# STSPIN.net
KiCad netlist of a schematic drawn in Altium Designer
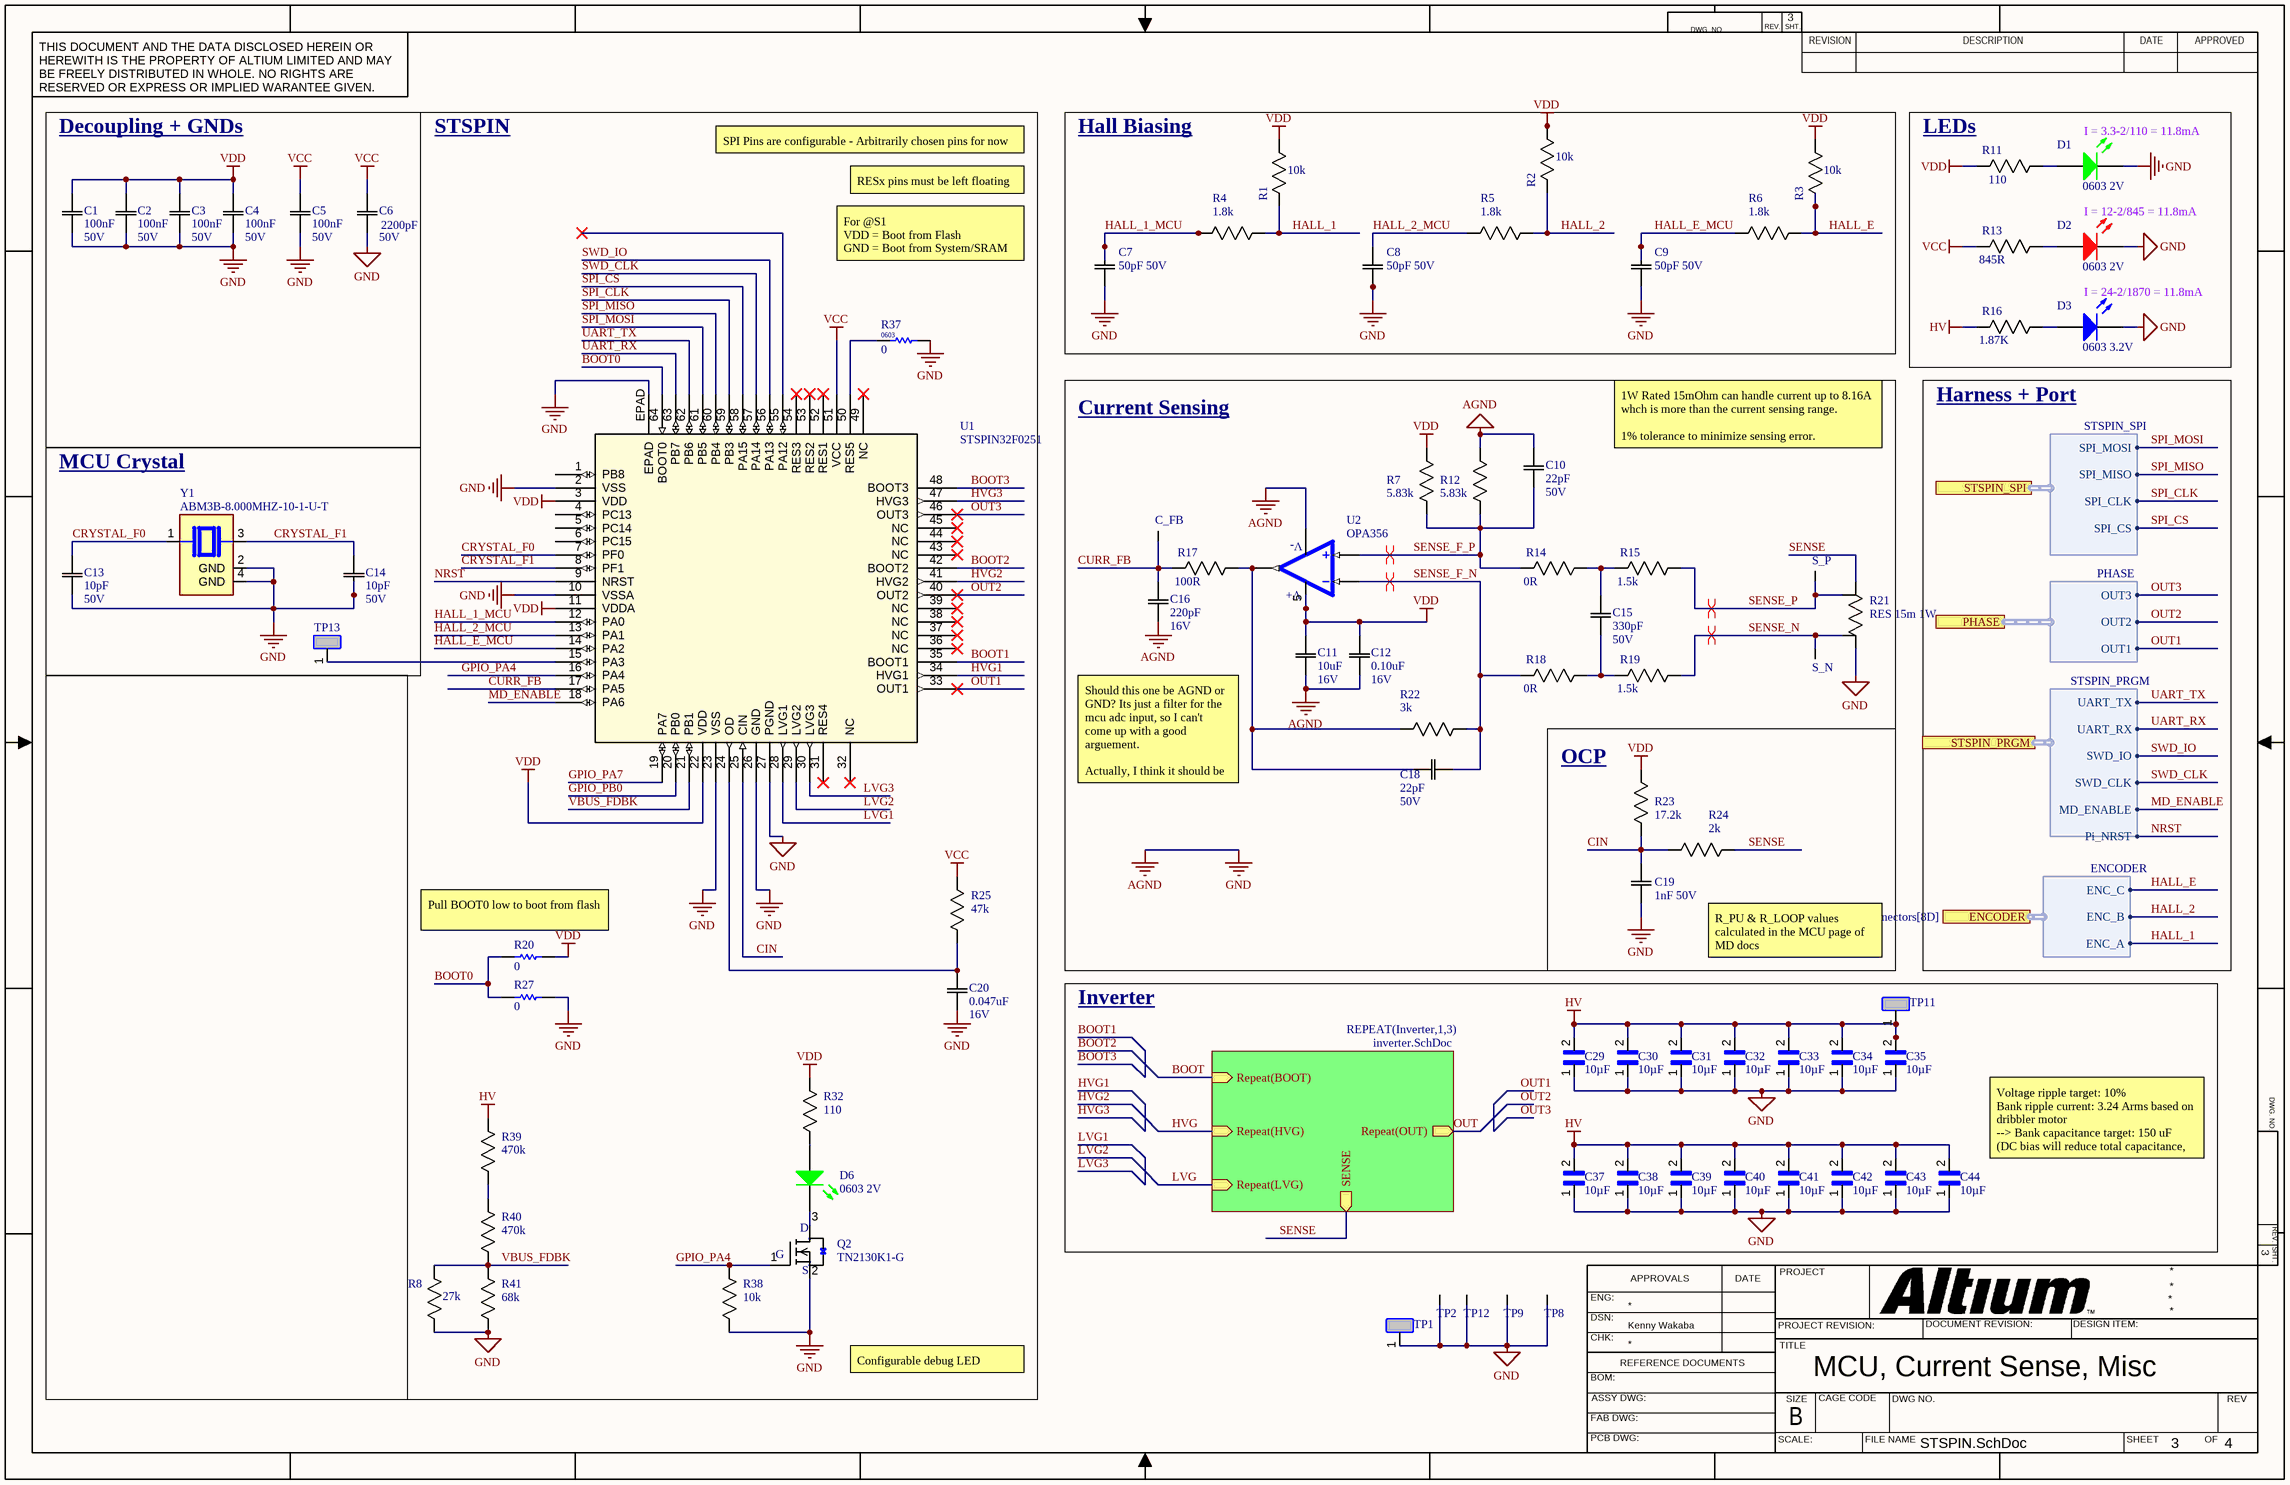
[diagram p0: STSPIN.SchDoc]

(export (version "E")
  (design (tool "Eeschema 10.0.6"))
  (components
    (comp (ref "C1")
      (value "100nF")
      (footprint "0603")
      (description "Default Symbol for Capacitors")
      (fields
        (field (name "RATING") "50V")
        (field (name "PART NUMBER") "CAP 100nF 50V")
        (field (name "TOLERANCE") "10%")
      )
      (libsource (lib "capacitor_library") (part "CAP_Default"))
    )
    (comp (ref "C2")
      (value "100nF")
      (footprint "0603")
      (description "Default Symbol for Capacitors")
      (fields
        (field (name "RATING") "50V")
        (field (name "PART NUMBER") "CAP 100nF 50V")
        (field (name "TOLERANCE") "10%")
      )
      (libsource (lib "capacitor_library") (part "CAP_Default"))
    )
    (comp (ref "C3")
      (value "100nF")
      (footprint "0603")
      (description "Default Symbol for Capacitors")
      (fields
        (field (name "RATING") "50V")
        (field (name "PART NUMBER") "CAP 100nF 50V")
        (field (name "TOLERANCE") "10%")
      )
      (libsource (lib "capacitor_library") (part "CAP_Default"))
    )
    (comp (ref "C4")
      (value "100nF")
      (footprint "0603")
      (description "Default Symbol for Capacitors")
      (fields
        (field (name "RATING") "50V")
        (field (name "PART NUMBER") "CAP 100nF 50V")
        (field (name "TOLERANCE") "10%")
      )
      (libsource (lib "capacitor_library") (part "CAP_Default"))
    )
    (comp (ref "C5")
      (value "100nF")
      (footprint "0603")
      (description "Default Symbol for Capacitors")
      (fields
        (field (name "RATING") "50V")
        (field (name "PART NUMBER") "CAP 100nF 50V")
        (field (name "TOLERANCE") "10%")
      )
      (libsource (lib "capacitor_library") (part "CAP_Default"))
    )
    (comp (ref "C6")
      (value "2200pF")
      (footprint "0603")
      (description "Default Symbol for Capacitors")
      (fields
        (field (name "RATING") "50V")
        (field (name "PART NUMBER") "CAP 2200pF 50V")
        (field (name "TOLERANCE") "10%")
      )
      (libsource (lib "capacitor_library") (part "CAP_Default"))
    )
    (comp (ref "C7")
      (value "50pF 50V")
      (footprint "0603")
      (description "50 pF ±5% 50V Ceramic Capacitor C0G, NP0 0603 (1608 Metric)")
      (fields (field (name "TOLERANCE") "10%"))
      (libsource (lib "MDV6-TEMP") (part "CAP 50pF 50V"))
    )
    (comp (ref "C8")
      (value "50pF 50V")
      (footprint "0603")
      (description "50 pF ±5% 50V Ceramic Capacitor C0G, NP0 0603 (1608 Metric)")
      (fields (field (name "TOLERANCE") "10%"))
      (libsource (lib "MDV6-TEMP") (part "CAP 50pF 50V"))
    )
    (comp (ref "C9")
      (value "50pF 50V")
      (footprint "0603")
      (description "50 pF ±5% 50V Ceramic Capacitor C0G, NP0 0603 (1608 Metric)")
      (fields (field (name "TOLERANCE") "10%"))
      (libsource (lib "MDV6-TEMP") (part "CAP 50pF 50V"))
    )
    (comp (ref "C10")
      (value "22pF")
      (footprint "0603")
      (description "Default Symbol for Capacitors")
      (fields
        (field (name "RATING") "50V")
        (field (name "PART NUMBER") "CAP 22pF 50V")
        (field (name "TOLERANCE") "10%")
      )
      (libsource (lib "capacitor_library") (part "CAP_Default"))
    )
    (comp (ref "C11")
      (value "10uF")
      (footprint "0603")
      (description "CAP CER 10UF 16V X5R 0603/0805")
      (fields
        (field (name "TOLERANCE") "10%")
        (field (name "RATING") "16V")
        (field (name "PART NUMBER") "CAP 10uF 16V")
      )
      (libsource (lib "capacitor_library") (part "CAP 10uF 16V"))
    )
    (comp (ref "C12")
      (value "0.10uF")
      (footprint "0603")
      (description "CAP CER 0.10UF 16V X5R 0603")
      (fields
        (field (name "TOLERANCE") "10%")
        (field (name "RATING") "16V")
        (field (name "PART NUMBER") "CAP 0.10uF 16V")
      )
      (libsource (lib "capacitor_library") (part "CAP 0.10uF 16V"))
    )
    (comp (ref "C13")
      (value "10pF")
      (footprint "0603")
      (description "Default Symbol for Capacitors")
      (fields
        (field (name "RATING") "50V")
        (field (name "PART NUMBER") "CAP 10pF 50V")
        (field (name "TOLERANCE") "10%")
      )
      (libsource (lib "capacitor_library") (part "CAP_Default"))
    )
    (comp (ref "C14")
      (value "10pF")
      (footprint "0603")
      (description "Default Symbol for Capacitors")
      (fields
        (field (name "RATING") "50V")
        (field (name "PART NUMBER") "CAP 10pF 50V")
        (field (name "TOLERANCE") "10%")
      )
      (libsource (lib "capacitor_library") (part "CAP_Default"))
    )
    (comp (ref "C15")
      (value "330pF")
      (footprint "0603")
      (description "Default Symbol for Capacitors")
      (fields
        (field (name "RATING") "50V")
        (field (name "PART NUMBER") "CAP 330pF 50V")
        (field (name "TOLERANCE") "10%")
      )
      (libsource (lib "capacitor_library") (part "CAP_Default"))
    )
    (comp (ref "C16")
      (value "220pF")
      (footprint "0603")
      (description "Default Symbol for Capacitors")
      (fields
        (field (name "RATING") "16V")
        (field (name "PART NUMBER") "CAP 220pF 16V")
        (field (name "TOLERANCE") "10%")
      )
      (libsource (lib "capacitor_library") (part "CAP_Default"))
    )
    (comp (ref "C18")
      (value "22pF")
      (footprint "0603")
      (description "Default Symbol for Capacitors")
      (fields
        (field (name "RATING") "50V")
        (field (name "PART NUMBER") "CAP 22pF 50V")
        (field (name "TOLERANCE") "10%")
      )
      (libsource (lib "capacitor_library") (part "CAP_Default"))
    )
    (comp (ref "C19")
      (value "1nF 50V")
      (footprint "0603")
      (description "CAP CER 0603 1NF 50V X7R 10%")
      (fields (field (name "TOLERANCE") "10%"))
      (libsource (lib "MDV6-TEMP") (part "CAP 1nF 50V"))
    )
    (comp (ref "C20")
      (value "0.047uF")
      (footprint "0603")
      (description "Default Symbol for Capacitors")
      (fields
        (field (name "RATING") "16V")
        (field (name "PART NUMBER") "CAP 0.047uF 16V")
        (field (name "TOLERANCE") "10%")
      )
      (libsource (lib "capacitor_library") (part "CAP_Default"))
    )
    (comp (ref "C29")
      (value "10µF")
      (footprint "CAPC2012X145N")
      (description "SMD capacitor X5R(EIA) with capacitance 10uF Tol.10%. Rated voltage 50Vdc 85C")
      (fields (field (name "MP") "GRM21BR61H106KE43K") (field (name "MF") "Murata"))
      (libsource (lib "UBC Thunderbots") (part "GRM21BR61H106KE43K"))
    )
    (comp (ref "C30")
      (value "10µF")
      (footprint "CAPC2012X145N")
      (description "SMD capacitor X5R(EIA) with capacitance 10uF Tol.10%. Rated voltage 50Vdc 85C")
      (fields (field (name "MP") "GRM21BR61H106KE43K") (field (name "MF") "Murata"))
      (libsource (lib "UBC Thunderbots") (part "GRM21BR61H106KE43K"))
    )
    (comp (ref "C31")
      (value "10µF")
      (footprint "CAPC2012X145N")
      (description "SMD capacitor X5R(EIA) with capacitance 10uF Tol.10%. Rated voltage 50Vdc 85C")
      (fields (field (name "MP") "GRM21BR61H106KE43K") (field (name "MF") "Murata"))
      (libsource (lib "UBC Thunderbots") (part "GRM21BR61H106KE43K"))
    )
    (comp (ref "C32")
      (value "10µF")
      (footprint "CAPC2012X145N")
      (description "SMD capacitor X5R(EIA) with capacitance 10uF Tol.10%. Rated voltage 50Vdc 85C")
      (fields (field (name "MP") "GRM21BR61H106KE43K") (field (name "MF") "Murata"))
      (libsource (lib "UBC Thunderbots") (part "GRM21BR61H106KE43K"))
    )
    (comp (ref "C33")
      (value "10µF")
      (footprint "CAPC2012X145N")
      (description "SMD capacitor X5R(EIA) with capacitance 10uF Tol.10%. Rated voltage 50Vdc 85C")
      (fields (field (name "MP") "GRM21BR61H106KE43K") (field (name "MF") "Murata"))
      (libsource (lib "UBC Thunderbots") (part "GRM21BR61H106KE43K"))
    )
    (comp (ref "C34")
      (value "10µF")
      (footprint "CAPC2012X145N")
      (description "SMD capacitor X5R(EIA) with capacitance 10uF Tol.10%. Rated voltage 50Vdc 85C")
      (fields (field (name "MP") "GRM21BR61H106KE43K") (field (name "MF") "Murata"))
      (libsource (lib "UBC Thunderbots") (part "GRM21BR61H106KE43K"))
    )
    (comp (ref "C35")
      (value "10µF")
      (footprint "CAPC2012X145N")
      (description "SMD capacitor X5R(EIA) with capacitance 10uF Tol.10%. Rated voltage 50Vdc 85C")
      (fields (field (name "MP") "GRM21BR61H106KE43K") (field (name "MF") "Murata"))
      (libsource (lib "UBC Thunderbots") (part "GRM21BR61H106KE43K"))
    )
    (comp (ref "C37")
      (value "10µF")
      (footprint "CAPC2012X145N")
      (description "SMD capacitor X5R(EIA) with capacitance 10uF Tol.10%. Rated voltage 50Vdc 85C")
      (fields (field (name "MP") "GRM21BR61H106KE43K") (field (name "MF") "Murata"))
      (libsource (lib "UBC Thunderbots") (part "GRM21BR61H106KE43K"))
    )
    (comp (ref "C38")
      (value "10µF")
      (footprint "CAPC2012X145N")
      (description "SMD capacitor X5R(EIA) with capacitance 10uF Tol.10%. Rated voltage 50Vdc 85C")
      (fields (field (name "MP") "GRM21BR61H106KE43K") (field (name "MF") "Murata"))
      (libsource (lib "UBC Thunderbots") (part "GRM21BR61H106KE43K"))
    )
    (comp (ref "C39")
      (value "10µF")
      (footprint "CAPC2012X145N")
      (description "SMD capacitor X5R(EIA) with capacitance 10uF Tol.10%. Rated voltage 50Vdc 85C")
      (fields (field (name "MP") "GRM21BR61H106KE43K") (field (name "MF") "Murata"))
      (libsource (lib "UBC Thunderbots") (part "GRM21BR61H106KE43K"))
    )
    (comp (ref "C40")
      (value "10µF")
      (footprint "CAPC2012X145N")
      (description "SMD capacitor X5R(EIA) with capacitance 10uF Tol.10%. Rated voltage 50Vdc 85C")
      (fields (field (name "MP") "GRM21BR61H106KE43K") (field (name "MF") "Murata"))
      (libsource (lib "UBC Thunderbots") (part "GRM21BR61H106KE43K"))
    )
    (comp (ref "C41")
      (value "10µF")
      (footprint "CAPC2012X145N")
      (description "SMD capacitor X5R(EIA) with capacitance 10uF Tol.10%. Rated voltage 50Vdc 85C")
      (fields (field (name "MP") "GRM21BR61H106KE43K") (field (name "MF") "Murata"))
      (libsource (lib "UBC Thunderbots") (part "GRM21BR61H106KE43K"))
    )
    (comp (ref "C42")
      (value "10µF")
      (footprint "CAPC2012X145N")
      (description "SMD capacitor X5R(EIA) with capacitance 10uF Tol.10%. Rated voltage 50Vdc 85C")
      (fields (field (name "MP") "GRM21BR61H106KE43K") (field (name "MF") "Murata"))
      (libsource (lib "UBC Thunderbots") (part "GRM21BR61H106KE43K"))
    )
    (comp (ref "C43")
      (value "10µF")
      (footprint "CAPC2012X145N")
      (description "SMD capacitor X5R(EIA) with capacitance 10uF Tol.10%. Rated voltage 50Vdc 85C")
      (fields (field (name "MP") "GRM21BR61H106KE43K") (field (name "MF") "Murata"))
      (libsource (lib "UBC Thunderbots") (part "GRM21BR61H106KE43K"))
    )
    (comp (ref "C44")
      (value "10µF")
      (footprint "CAPC2012X145N")
      (description "SMD capacitor X5R(EIA) with capacitance 10uF Tol.10%. Rated voltage 50Vdc 85C")
      (fields (field (name "MP") "GRM21BR61H106KE43K") (field (name "MF") "Murata"))
      (libsource (lib "UBC Thunderbots") (part "GRM21BR61H106KE43K"))
    )
    (comp (ref "C_FB")
      (value "Test Point (Via)")
      (footprint "TP")
      (libsource (lib "UBC Thunderbots") (part "Test Point (Via)"))
    )
    (comp (ref "D1")
      (value "0603 2V")
      (footprint "0603 - LED")
      (description "Green 570nm LED Indication - Discrete 2V 0603 (1608 Metric)")
      (libsource (lib "MDV6-TEMP") (part "LED GREEN SMD 0603"))
    )
    (comp (ref "D2")
      (value "0603 2V")
      (footprint "0603 - LED")
      (description "Red 625nm LED Indication - Discrete 2V 0603 (1608 Metric)")
      (libsource (lib "MDV6-TEMP") (part "LED RED SMD 0603"))
    )
    (comp (ref "D3")
      (value "0603 3.2V")
      (footprint "0603 - LED")
      (description "Blue 470nm LED Indication - Discrete 3.2V 0603 (1608 Metric)")
      (libsource (lib "MDV6-TEMP") (part "LED BLUE SMD 0603"))
    )
    (comp (ref "D6")
      (value "0603 2V")
      (footprint "0603 - LED")
      (description "Green 570nm LED Indication - Discrete 2V 0603 (1608 Metric)")
      (libsource (lib "MDV6-TEMP") (part "LED GREEN SMD 0603"))
    )
    (comp (ref "Q2")
      (value "TN2130K1-G")
      (footprint "SOT95P237X112-3N")
      (description "N-Channel 300 V 85mA (Tj) 360mW (Tc) Surface Mount TO-236AB (SOT23)")
      (fields
        (field (name "PART NUMBER") "MOSFET N-CH TN2130K1-G")
        (field (name "COPYRIGHT") "Copyright (C) 2021 Ultra Librarian. All rights reserved.")
      )
      (libsource (lib "Transistor_Library") (part "MOSFET N-CH TN2130K1-G"))
    )
    (comp (ref "R1")
      (value "10k")
      (footprint "0603")
      (description "RES 10k 1/8W - 1%")
      (fields (field (name "TOLERANCE") "5%"))
      (libsource (lib "UBC Thunderbots") (part "RES_DEFAULT"))
    )
    (comp (ref "R2")
      (value "10k")
      (footprint "0603")
      (description "RES 10k 1/8W - 1%")
      (fields (field (name "TOLERANCE") "5%"))
      (libsource (lib "UBC Thunderbots") (part "RES_DEFAULT"))
    )
    (comp (ref "R3")
      (value "10k")
      (footprint "0603")
      (description "RES 10k 1/8W - 1%")
      (fields (field (name "TOLERANCE") "5%"))
      (libsource (lib "UBC Thunderbots") (part "RES_DEFAULT"))
    )
    (comp (ref "R4")
      (value "1.8k")
      (footprint "0603")
      (description "Default Resistor Symbol")
      (fields (field (name "TOLERANCE") "5%") (field (name "PART NUMBER") "RES 1.8k 1/8W"))
      (libsource (lib "") (part "RES_DEFAULT_1"))
    )
    (comp (ref "R5")
      (value "1.8k")
      (footprint "0603")
      (description "Default Resistor Symbol")
      (fields (field (name "TOLERANCE") "5%") (field (name "PART NUMBER") "RES 1.8k 1/8W"))
      (libsource (lib "") (part "RES_DEFAULT_1"))
    )
    (comp (ref "R6")
      (value "1.8k")
      (footprint "0603")
      (description "Default Resistor Symbol")
      (fields (field (name "TOLERANCE") "5%") (field (name "PART NUMBER") "RES 1.8k 1/8W"))
      (libsource (lib "") (part "RES_DEFAULT_1"))
    )
    (comp (ref "R7")
      (value "5.83k")
      (footprint "0603")
      (description "RES 5.83K OHM 0.1% 1/10W 0603")
      (fields (field (name "TOLERANCE") "1%"))
      (libsource (lib "MDV6-TEMP") (part "RES 5.83k 1/10W 0.1%"))
    )
    (comp (ref "R8")
      (value "27k")
      (footprint "0603")
      (description "RES 27k 1/8W")
      (libsource (lib "UBC Thunderbots") (part "RES_DEFAULT"))
    )
    (comp (ref "R11")
      (value "110")
      (footprint "0603")
      (description "Default Resistor Symbol")
      (fields (field (name "TOLERANCE") "1%") (field (name "PART NUMBER") "RES 110.0 1/8W - 1%"))
      (libsource (lib "Resistor_Library") (part "RES_DEFAULT"))
    )
    (comp (ref "R12")
      (value "5.83k")
      (footprint "0603")
      (description "RES 5.83K OHM 0.1% 1/10W 0603")
      (fields (field (name "TOLERANCE") "1%"))
      (libsource (lib "MDV6-TEMP") (part "RES 5.83k 1/10W 0.1%"))
    )
    (comp (ref "R13")
      (value "845R")
      (footprint "0603")
      (description "RES 845 OHM 1% 1/10W 0603")
      (fields (field (name "TOLERANCE") "1%"))
      (libsource (lib "MDV6-TEMP") (part "RES 845 1/10W 1%"))
    )
    (comp (ref "R14")
      (value "0R")
      (footprint "0603")
      (description "0 OHM 1/10W 0603")
      (fields (field (name "TOLERANCE") "1%"))
      (libsource (lib "") (part "RES 100R 1/10W 0.05%_1"))
    )
    (comp (ref "R15")
      (value "1.5k")
      (footprint "0603")
      (description "RES SMD 1.5k OHM 0.05% 1/10W 0603")
      (fields (field (name "TOLERANCE") "1%"))
      (libsource (lib "") (part "RES 100R 1/10W 0.05%_1"))
    )
    (comp (ref "R16")
      (value "1.87K")
      (footprint "0603")
      (description "RES 1.87K OHM 1% 1/10W 0603")
      (fields (field (name "TOLERANCE") "1%"))
      (libsource (lib "MDV6-TEMP") (part "RES 1.87K 1/10W 1%"))
    )
    (comp (ref "R17")
      (value "100R")
      (footprint "0603")
      (description "RES SMD 100 OHM 0.05% 1/10W 0603")
      (fields (field (name "TOLERANCE") "1%"))
      (libsource (lib "MDV6-TEMP") (part "RES 100R 1/10W 0.05%"))
    )
    (comp (ref "R18")
      (value "0R")
      (footprint "0603")
      (description "0 OHM  1/10W 0603")
      (fields (field (name "TOLERANCE") "1%"))
      (libsource (lib "") (part "RES 100R 1/10W 0.05%_1"))
    )
    (comp (ref "R19")
      (value "1.5k")
      (footprint "0603")
      (description "RES SMD 1.5k OHM 0.05% 1/10W 0603")
      (fields (field (name "TOLERANCE") "1%"))
      (libsource (lib "") (part "RES 100R 1/10W 0.05%_1"))
    )
    (comp (ref "R20")
      (value "0")
      (footprint "RESC1005X40X25ML05T10")
      (description "Chip Resistor, 0 Ohm, 0.063 W, -55 to 155 degC, 0402 (1005 Metric)")
      (fields (field (name "POWER") "63mW") (field (name "Comment") "Resistor 0R 0402 63 mW"))
      (libsource (lib "") (part "RES-2_1"))
    )
    (comp (ref "R21")
      (value "RES 15m 1W")
      (footprint "1206 - Current Sense")
      (description "1W 0.015 OHM METAL ALLOY CS 1% C 1206")
      (libsource (lib "MDV6-TEMP") (part "RES 15m 1W"))
    )
    (comp (ref "R22")
      (value "3k")
      (footprint "0603")
      (description "RES 3K OHM 0.1% 1/10W 0603")
      (fields (field (name "TOLERANCE") "1%"))
      (libsource (lib "") (part "RES 5.83k 1/10W 0.1%_1"))
    )
    (comp (ref "R23")
      (value "17.2k")
      (footprint "0603")
      (description "RES 17.2k OHM 0.1% 1/10W 0603")
      (fields (field (name "TOLERANCE") "1%"))
      (libsource (lib "MDV6-TEMP") (part "RES 17.2k 1/10W 0.1%"))
    )
    (comp (ref "R24")
      (value "2k")
      (footprint "0603")
      (description "Default Resistor Symbol")
      (fields (field (name "TOLERANCE") "5%") (field (name "PART NUMBER") "RES 2k 1/8W"))
      (libsource (lib "") (part "RES_DEFAULT_1"))
    )
    (comp (ref "R25")
      (value "47k")
      (footprint "0603")
      (description "Default Resistor Symbol")
      (fields (field (name "TOLERANCE") "1%") (field (name "PART NUMBER") "RES 47k 1/8W - 1%"))
      (libsource (lib "") (part "RES_DEFAULT_1"))
    )
    (comp (ref "R27")
      (value "0")
      (footprint "RESC1005X40X25ML05T10")
      (description "Chip Resistor, 0 Ohm, 0.063 W, -55 to 155 degC, 0402 (1005 Metric)")
      (fields (field (name "POWER") "63mW") (field (name "Comment") "Resistor 0R 0402 63 mW"))
      (libsource (lib "") (part "RES-2_1"))
    )
    (comp (ref "R32")
      (value "110")
      (footprint "0603")
      (description "Default Resistor Symbol")
      (fields (field (name "TOLERANCE") "1%") (field (name "PART NUMBER") "RES 110.0 1/8W - 1%"))
      (libsource (lib "") (part "RES_DEFAULT_1"))
    )
    (comp (ref "R37")
      (value "0")
      (footprint "0603 IPC Class B")
      (description "Fixed Resistor, Metal Glaze/thick Film, 0.1W, 0ohm, Surface Mount, 0603")
      (fields (field (name "POWER") "100mW") (field (name "Comment") "Resistor 0R 0.1W 0603"))
      (libsource (lib "UBC Thunderbots") (part "RES-2"))
    )
    (comp (ref "R38")
      (value "10k")
      (footprint "0603")
      (description "Default Resistor Symbol")
      (fields (field (name "TOLERANCE") "5%") (field (name "PART NUMBER") "RES 10k 1/8W - 1%"))
      (libsource (lib "Resistor_Library") (part "RES_DEFAULT"))
    )
    (comp (ref "R39")
      (value "470k")
      (footprint "0603")
      (description "Default Resistor Symbol")
      (fields (field (name "TOLERANCE") "5%") (field (name "PART NUMBER") "RES 470k 1/8W"))
      (libsource (lib "Resistor_Library") (part "RES_DEFAULT"))
    )
    (comp (ref "R40")
      (value "470k")
      (footprint "0603")
      (description "Default Resistor Symbol")
      (fields (field (name "TOLERANCE") "5%") (field (name "PART NUMBER") "RES 470k 1/8W"))
      (libsource (lib "") (part "RES_DEFAULT_1"))
    )
    (comp (ref "R41")
      (value "68k")
      (footprint "0603")
      (description "Default Resistor Symbol")
      (fields (field (name "TOLERANCE") "5%") (field (name "PART NUMBER") "RES 68k 1/8W"))
      (libsource (lib "") (part "RES_DEFAULT_1"))
    )
    (comp (ref "S_N")
      (value "Test Point (Via)")
      (footprint "TP")
      (libsource (lib "UBC Thunderbots") (part "Test Point (Via)"))
    )
    (comp (ref "S_P")
      (value "Test Point (Via)")
      (footprint "TP")
      (libsource (lib "UBC Thunderbots") (part "Test Point (Via)"))
    )
    (comp (ref "TP1")
      (value "RCT-0C")
      (footprint "RCT-0C-Footprint-1")
      (description "Metal Foil, 0W, 0.05ohm, Surface Mount, 0805")
      (libsource (lib "UBC Thunderbots") (part "RCT-0C"))
    )
    (comp (ref "TP2")
      (value "Test Point (Via)")
      (footprint "TP")
      (libsource (lib "UBC Thunderbots") (part "Test Point (Via)"))
    )
    (comp (ref "TP8")
      (value "Test Point (Via)")
      (footprint "TP")
      (libsource (lib "UBC Thunderbots") (part "Test Point (Via)"))
    )
    (comp (ref "TP9")
      (value "Test Point (Via)")
      (footprint "TP")
      (libsource (lib "UBC Thunderbots") (part "Test Point (Via)"))
    )
    (comp (ref "TP11")
      (value "RCT-0C")
      (footprint "RCT-0C-Footprint-1")
      (description "Metal Foil, 0W, 0.05ohm, Surface Mount, 0805")
      (libsource (lib "UBC Thunderbots") (part "RCT-0C"))
    )
    (comp (ref "TP12")
      (value "Test Point (Via)")
      (footprint "TP")
      (libsource (lib "UBC Thunderbots") (part "Test Point (Via)"))
    )
    (comp (ref "TP13")
      (value "RCT-0C")
      (footprint "RCT-0C-Footprint-1")
      (description "Metal Foil, 0W, 0.05ohm, Surface Mount, 0805")
      (libsource (lib "UBC Thunderbots") (part "RCT-0C"))
    )
    (comp (ref "U1")
      (value "STSPIN32F0251")
      (footprint "TQFP64_10X10_STM-M")
      (description "No Description Available")
      (libsource (lib "MDV6-TEMP") (part "STSPIN32F0251"))
    )
    (comp (ref "U2")
      (value "OPA356")
      (footprint "SOT-23-5_MC_MCH-L")
      (description "IC OPAMP VFB 1 CIRCUIT SOT23-5")
      (fields
        (field (name "MANUFACTURER") "Analog Devices")
        (field (name "MANUFACTURER PART NUMBER") "ADA4505-1ARJZ-R7")
      )
      (libsource (lib "MDV6-TEMP") (part "OPA356"))
    )
    (comp (ref "Y1")
      (value "ABM3B-8.000MHZ-10-1-U-T")
      (footprint "XTAL_ABM3B-8.000MHZ-10-1-U-T")
      (description "8 MHz Â±10ppm Crystal 10pF 200 Ohms 4-SMD, No Lead")
      (fields (field (name "MF") "Abracon"))
      (libsource (lib "ABM3B-8.000MHZ-10-1-U-T") (part "ABM3B-8.000MHZ-10-1-U-T"))
    )
  )
  (nets
    (net (code "6") (name "/BOOT0") (class "Default")
      (node (ref "R20") (pin "1") (pinfunction "1_1") (pintype "passive"))
      (node (ref "R27") (pin "1") (pinfunction "1_1") (pintype "passive"))
      (node (ref "U1") (pin "64") (pinfunction "BOOT0_64") (pintype "input"))
    )
    (net (code "7") (name "/BOOT1") (class "Default")
      (node (ref "U1") (pin "35") (pinfunction "BOOT1_35") (pintype "power_in"))
    )
    (net (code "8") (name "/BOOT2") (class "Default")
      (node (ref "U1") (pin "42") (pinfunction "BOOT2_42") (pintype "power_in"))
    )
    (net (code "9") (name "/BOOT3") (class "Default")
      (node (ref "U1") (pin "48") (pinfunction "BOOT3_48") (pintype "power_in"))
    )
    (net (code "10") (name "/CIN") (class "Default")
      (node (ref "C19") (pin "2") (pinfunction "C2_2") (pintype "passive"))
      (node (ref "R23") (pin "2") (pinfunction "R2_2") (pintype "passive"))
      (node (ref "R24") (pin "2") (pinfunction "R2_2") (pintype "passive"))
      (node (ref "U1") (pin "25") (pinfunction "CIN_25") (pintype "input"))
    )
    (net (code "11") (name "/CRYSTAL_F0") (class "Default")
      (node (ref "C13") (pin "2") (pinfunction "C2_2") (pintype "passive"))
      (node (ref "U1") (pin "7") (pinfunction "PF0_7") (pintype "bidirectional"))
      (node (ref "Y1") (pin "1") (pinfunction "1_1") (pintype "passive"))
    )
    (net (code "12") (name "/CRYSTAL_F1") (class "Default")
      (node (ref "C14") (pin "2") (pinfunction "C2_2") (pintype "passive"))
      (node (ref "U1") (pin "8") (pinfunction "PF1_8") (pintype "bidirectional"))
      (node (ref "Y1") (pin "3") (pinfunction "2_3") (pintype "passive"))
    )
    (net (code "13") (name "/CURR_FB") (class "Default")
      (node (ref "C16") (pin "2") (pinfunction "C2_2") (pintype "passive"))
      (node (ref "C_FB") (pin "1") (pinfunction "1_1") (pintype "passive"))
      (node (ref "R17") (pin "2") (pinfunction "R2_2") (pintype "passive"))
      (node (ref "U1") (pin "17") (pinfunction "PA5_17") (pintype "bidirectional"))
    )
    (net (code "14") (name "/GPIO_PA4") (class "Default")
      (node (ref "Q2") (pin "1") (pinfunction "G_1") (pintype "passive"))
      (node (ref "R38") (pin "2") (pinfunction "R2_2") (pintype "passive"))
      (node (ref "U1") (pin "16") (pinfunction "PA4_16") (pintype "bidirectional"))
    )
    (net (code "15") (name "/GPIO_PA7") (class "Default")
      (node (ref "U1") (pin "19") (pinfunction "PA7_19") (pintype "bidirectional"))
    )
    (net (code "16") (name "/GPIO_PB0") (class "Default")
      (node (ref "U1") (pin "20") (pinfunction "PB0_20") (pintype "bidirectional"))
    )
    (net (code "17") (name "/HALL_1") (class "Default")
      (node (ref "R1") (pin "2") (pinfunction "R2_2") (pintype "passive"))
      (node (ref "R4") (pin "1") (pinfunction "R1_1") (pintype "passive"))
    )
    (net (code "18") (name "/HALL_1_MCU") (class "Default")
      (node (ref "C7") (pin "2") (pinfunction "C2_2") (pintype "passive"))
      (node (ref "R4") (pin "2") (pinfunction "R2_2") (pintype "passive"))
      (node (ref "U1") (pin "12") (pinfunction "PA0_12") (pintype "bidirectional"))
    )
    (net (code "19") (name "/HALL_2") (class "Default")
      (node (ref "R2") (pin "2") (pinfunction "R2_2") (pintype "passive"))
      (node (ref "R5") (pin "1") (pinfunction "R1_1") (pintype "passive"))
    )
    (net (code "20") (name "/HALL_2_MCU") (class "Default")
      (node (ref "C8") (pin "2") (pinfunction "C2_2") (pintype "passive"))
      (node (ref "R5") (pin "2") (pinfunction "R2_2") (pintype "passive"))
      (node (ref "U1") (pin "13") (pinfunction "PA1_13") (pintype "bidirectional"))
    )
    (net (code "21") (name "/HALL_E") (class "Default")
      (node (ref "R3") (pin "2") (pinfunction "R2_2") (pintype "passive"))
      (node (ref "R6") (pin "1") (pinfunction "R1_1") (pintype "passive"))
    )
    (net (code "22") (name "/HALL_E_MCU") (class "Default")
      (node (ref "C9") (pin "2") (pinfunction "C2_2") (pintype "passive"))
      (node (ref "R6") (pin "2") (pinfunction "R2_2") (pintype "passive"))
      (node (ref "U1") (pin "14") (pinfunction "PA2_14") (pintype "bidirectional"))
    )
    (net (code "24") (name "/HVG1") (class "Default")
      (node (ref "U1") (pin "34") (pinfunction "HVG1_34") (pintype "output"))
    )
    (net (code "25") (name "/HVG2") (class "Default")
      (node (ref "U1") (pin "41") (pinfunction "HVG2_41") (pintype "output"))
    )
    (net (code "26") (name "/HVG3") (class "Default")
      (node (ref "U1") (pin "47") (pinfunction "HVG3_47") (pintype "output"))
    )
    (net (code "28") (name "/LVG1") (class "Default")
      (node (ref "U1") (pin "28") (pinfunction "LVG1_28") (pintype "output"))
    )
    (net (code "29") (name "/LVG2") (class "Default")
      (node (ref "U1") (pin "29") (pinfunction "LVG2_29") (pintype "output"))
    )
    (net (code "30") (name "/LVG3") (class "Default")
      (node (ref "U1") (pin "30") (pinfunction "LVG3_30") (pintype "output"))
    )
    (net (code "31") (name "/MD_ENABLE") (class "Default")
      (node (ref "U1") (pin "18") (pinfunction "PA6_18") (pintype "bidirectional"))
    )
    (net (code "32") (name "/NRST") (class "Default")
      (node (ref "U1") (pin "9") (pinfunction "NRST_9") (pintype "passive"))
    )
    (net (code "34") (name "/OUT1") (class "Default")
      (node (ref "U1") (pin "33") (pinfunction "OUT1_33") (pintype "output"))
    )
    (net (code "35") (name "/OUT2") (class "Default")
      (node (ref "U1") (pin "40") (pinfunction "OUT2_40") (pintype "output"))
    )
    (net (code "36") (name "/OUT3") (class "Default")
      (node (ref "U1") (pin "46") (pinfunction "OUT3_46") (pintype "output"))
    )
    (net (code "37") (name "/SENSE") (class "Default")
      (node (ref "R21") (pin "1") (pinfunction "1_1") (pintype "passive"))
      (node (ref "R24") (pin "1") (pinfunction "R1_1") (pintype "passive"))
    )
    (net (code "38") (name "/SENSE_F_N") (class "Default")
      (node (ref "C18") (pin "2") (pinfunction "C2_2") (pintype "passive"))
      (node (ref "R18") (pin "2") (pinfunction "R2_2") (pintype "passive"))
      (node (ref "R22") (pin "1") (pinfunction "R1_1") (pintype "passive"))
      (node (ref "U2") (pin "4") (pinfunction "IN-_4") (pintype "input"))
    )
    (net (code "39") (name "/SENSE_F_P") (class "Default")
      (node (ref "C10") (pin "1") (pinfunction "C1_1") (pintype "passive"))
      (node (ref "R12") (pin "2") (pinfunction "R2_2") (pintype "passive"))
      (node (ref "R14") (pin "2") (pinfunction "R2_2") (pintype "passive"))
      (node (ref "R7") (pin "2") (pinfunction "R2_2") (pintype "passive"))
      (node (ref "U2") (pin "3") (pinfunction "IN+_3") (pintype "input"))
    )
    (net (code "40") (name "/SENSE_N") (class "Default")
      (node (ref "R19") (pin "1") (pinfunction "R1_1") (pintype "passive"))
      (node (ref "R21") (pin "S2") (pinfunction "S2_S2") (pintype "passive"))
      (node (ref "S_N") (pin "1") (pinfunction "1_1") (pintype "passive"))
    )
    (net (code "41") (name "/SENSE_P") (class "Default")
      (node (ref "R15") (pin "1") (pinfunction "R1_1") (pintype "passive"))
      (node (ref "R21") (pin "S1") (pinfunction "S1_S1") (pintype "passive"))
      (node (ref "S_P") (pin "1") (pinfunction "1_1") (pintype "passive"))
    )
    (net (code "42") (name "/SPI_CLK") (class "Default")
      (node (ref "U1") (pin "59") (pinfunction "PB3_59") (pintype "bidirectional"))
    )
    (net (code "43") (name "/SPI_CS") (class "Default")
      (node (ref "U1") (pin "58") (pinfunction "PA15_58") (pintype "bidirectional"))
    )
    (net (code "44") (name "/SPI_MISO") (class "Default")
      (node (ref "U1") (pin "60") (pinfunction "PB4_60") (pintype "bidirectional"))
    )
    (net (code "45") (name "/SPI_MOSI") (class "Default")
      (node (ref "U1") (pin "61") (pinfunction "PB5_61") (pintype "bidirectional"))
    )
    (net (code "46") (name "/SWD_CLK") (class "Default")
      (node (ref "U1") (pin "57") (pinfunction "PA14_57") (pintype "bidirectional"))
    )
    (net (code "47") (name "/SWD_IO") (class "Default")
      (node (ref "U1") (pin "56") (pinfunction "PA13_56") (pintype "bidirectional"))
    )
    (net (code "48") (name "/UART_RX") (class "Default")
      (node (ref "U1") (pin "63") (pinfunction "PB7_63") (pintype "bidirectional"))
    )
    (net (code "49") (name "/UART_TX") (class "Default")
      (node (ref "U1") (pin "62") (pinfunction "PB6_62") (pintype "bidirectional"))
    )
    (net (code "50") (name "/VBUS_FDBK") (class "Default")
      (node (ref "R40") (pin "2") (pinfunction "R2_2") (pintype "passive"))
      (node (ref "R41") (pin "2") (pinfunction "R2_2") (pintype "passive"))
      (node (ref "R8") (pin "1") (pinfunction "R1_1") (pintype "passive"))
      (node (ref "U1") (pin "21") (pinfunction "PB1_21") (pintype "bidirectional"))
    )
    (net (code "55") (name "AGND") (class "Default")
      (node (ref "C1") (pin "1") (pinfunction "C1_1") (pintype "passive"))
      (node (ref "C10") (pin "2") (pinfunction "C2_2") (pintype "passive"))
      (node (ref "C11") (pin "1") (pinfunction "C1_1") (pintype "passive"))
      (node (ref "C12") (pin "1") (pinfunction "C1_1") (pintype "passive"))
      (node (ref "C13") (pin "1") (pinfunction "C1_1") (pintype "passive"))
      (node (ref "C14") (pin "1") (pinfunction "C1_1") (pintype "passive"))
      (node (ref "C16") (pin "1") (pinfunction "C1_1") (pintype "passive"))
      (node (ref "C19") (pin "1") (pinfunction "C1_1") (pintype "passive"))
      (node (ref "C2") (pin "1") (pinfunction "C1_1") (pintype "passive"))
      (node (ref "C20") (pin "1") (pinfunction "C1_1") (pintype "passive"))
      (node (ref "C29") (pin "1") (pinfunction "1_1") (pintype "passive"))
      (node (ref "C3") (pin "1") (pinfunction "C1_1") (pintype "passive"))
      (node (ref "C30") (pin "1") (pinfunction "1_1") (pintype "passive"))
      (node (ref "C31") (pin "1") (pinfunction "1_1") (pintype "passive"))
      (node (ref "C32") (pin "1") (pinfunction "1_1") (pintype "passive"))
      (node (ref "C33") (pin "1") (pinfunction "1_1") (pintype "passive"))
      (node (ref "C34") (pin "1") (pinfunction "1_1") (pintype "passive"))
      (node (ref "C35") (pin "1") (pinfunction "1_1") (pintype "passive"))
      (node (ref "C37") (pin "1") (pinfunction "1_1") (pintype "passive"))
      (node (ref "C38") (pin "1") (pinfunction "1_1") (pintype "passive"))
      (node (ref "C39") (pin "1") (pinfunction "1_1") (pintype "passive"))
      (node (ref "C4") (pin "1") (pinfunction "C1_1") (pintype "passive"))
      (node (ref "C40") (pin "1") (pinfunction "1_1") (pintype "passive"))
      (node (ref "C41") (pin "1") (pinfunction "1_1") (pintype "passive"))
      (node (ref "C42") (pin "1") (pinfunction "1_1") (pintype "passive"))
      (node (ref "C43") (pin "1") (pinfunction "1_1") (pintype "passive"))
      (node (ref "C44") (pin "1") (pinfunction "1_1") (pintype "passive"))
      (node (ref "C5") (pin "1") (pinfunction "C1_1") (pintype "passive"))
      (node (ref "C6") (pin "1") (pinfunction "C1_1") (pintype "passive"))
      (node (ref "C7") (pin "1") (pinfunction "C1_1") (pintype "passive"))
      (node (ref "C8") (pin "1") (pinfunction "C1_1") (pintype "passive"))
      (node (ref "C9") (pin "1") (pinfunction "C1_1") (pintype "passive"))
      (node (ref "D1") (pin "2") (pinfunction "K_2") (pintype "passive"))
      (node (ref "D2") (pin "2") (pinfunction "K_2") (pintype "passive"))
      (node (ref "D3") (pin "2") (pinfunction "K_2") (pintype "passive"))
      (node (ref "Q2") (pin "2") (pinfunction "S_2") (pintype "passive"))
      (node (ref "R12") (pin "1") (pinfunction "R1_1") (pintype "passive"))
      (node (ref "R21") (pin "2") (pinfunction "2_2") (pintype "passive"))
      (node (ref "R27") (pin "2") (pinfunction "2_2") (pintype "passive"))
      (node (ref "R37") (pin "2") (pinfunction "2_2") (pintype "passive"))
      (node (ref "R38") (pin "1") (pinfunction "R1_1") (pintype "passive"))
      (node (ref "R41") (pin "1") (pinfunction "R1_1") (pintype "passive"))
      (node (ref "R8") (pin "2") (pinfunction "R2_2") (pintype "passive"))
      (node (ref "TP1") (pin "1") (pinfunction "SIGNAL_1") (pintype "passive"))
      (node (ref "TP12") (pin "1") (pinfunction "1_1") (pintype "passive"))
      (node (ref "TP2") (pin "1") (pinfunction "1_1") (pintype "passive"))
      (node (ref "TP8") (pin "1") (pinfunction "1_1") (pintype "passive"))
      (node (ref "TP9") (pin "1") (pinfunction "1_1") (pintype "passive"))
      (node (ref "U1") (pin "10") (pinfunction "VSSA_10") (pintype "power_in"))
      (node (ref "U1") (pin "2") (pinfunction "VSS_2") (pintype "power_in"))
      (node (ref "U1") (pin "23") (pinfunction "VSS_23") (pintype "power_in"))
      (node (ref "U1") (pin "26") (pinfunction "GND_26") (pintype "power_in"))
      (node (ref "U1") (pin "27") (pinfunction "PGND_27") (pintype "power_in"))
      (node (ref "U1") (pin "EPAD") (pinfunction "EPAD_EPAD") (pintype "power_in"))
      (node (ref "U2") (pin "2") (pinfunction "V-_2") (pintype "power_in"))
      (node (ref "Y1") (pin "2") (pinfunction "GND_2") (pintype "power_in"))
      (node (ref "Y1") (pin "4") (pinfunction "GND_4") (pintype "power_in"))
    )
    (net (code "56") (name "HV") (class "Default")
      (node (ref "C29") (pin "2") (pinfunction "2_2") (pintype "passive"))
      (node (ref "C30") (pin "2") (pinfunction "2_2") (pintype "passive"))
      (node (ref "C31") (pin "2") (pinfunction "2_2") (pintype "passive"))
      (node (ref "C32") (pin "2") (pinfunction "2_2") (pintype "passive"))
      (node (ref "C33") (pin "2") (pinfunction "2_2") (pintype "passive"))
      (node (ref "C34") (pin "2") (pinfunction "2_2") (pintype "passive"))
      (node (ref "C35") (pin "2") (pinfunction "2_2") (pintype "passive"))
      (node (ref "C37") (pin "2") (pinfunction "2_2") (pintype "passive"))
      (node (ref "C38") (pin "2") (pinfunction "2_2") (pintype "passive"))
      (node (ref "C39") (pin "2") (pinfunction "2_2") (pintype "passive"))
      (node (ref "C40") (pin "2") (pinfunction "2_2") (pintype "passive"))
      (node (ref "C41") (pin "2") (pinfunction "2_2") (pintype "passive"))
      (node (ref "C42") (pin "2") (pinfunction "2_2") (pintype "passive"))
      (node (ref "C43") (pin "2") (pinfunction "2_2") (pintype "passive"))
      (node (ref "C44") (pin "2") (pinfunction "2_2") (pintype "passive"))
      (node (ref "R16") (pin "2") (pinfunction "R2_2") (pintype "passive"))
      (node (ref "R39") (pin "1") (pinfunction "R1_1") (pintype "passive"))
      (node (ref "TP11") (pin "1") (pinfunction "SIGNAL_1") (pintype "passive"))
    )
    (net (code "57") (name "Net-(C15-C1)") (class "Default")
      (node (ref "C15") (pin "1") (pinfunction "C1_1") (pintype "passive"))
      (node (ref "R18") (pin "1") (pinfunction "R1_1") (pintype "passive"))
      (node (ref "R19") (pin "2") (pinfunction "R2_2") (pintype "passive"))
    )
    (net (code "58") (name "Net-(C15-C2)") (class "Default")
      (node (ref "C15") (pin "2") (pinfunction "C2_2") (pintype "passive"))
      (node (ref "R14") (pin "1") (pinfunction "R1_1") (pintype "passive"))
      (node (ref "R15") (pin "2") (pinfunction "R2_2") (pintype "passive"))
    )
    (net (code "59") (name "Net-(C18-C1)") (class "Default")
      (node (ref "C18") (pin "1") (pinfunction "C1_1") (pintype "passive"))
      (node (ref "R17") (pin "1") (pinfunction "R1_1") (pintype "passive"))
      (node (ref "R22") (pin "2") (pinfunction "R2_2") (pintype "passive"))
      (node (ref "U2") (pin "1") (pinfunction "OUT_1") (pintype "output"))
    )
    (net (code "60") (name "Net-(C20-C2)") (class "Default")
      (node (ref "C20") (pin "2") (pinfunction "C2_2") (pintype "passive"))
      (node (ref "R25") (pin "1") (pinfunction "R1_1") (pintype "passive"))
      (node (ref "U1") (pin "24") (pinfunction "OD_24") (pintype "output"))
    )
    (net (code "61") (name "Net-(D1-A)") (class "Default")
      (node (ref "D1") (pin "1") (pinfunction "A_1") (pintype "passive"))
      (node (ref "R11") (pin "1") (pinfunction "R1_1") (pintype "passive"))
    )
    (net (code "62") (name "Net-(D2-A)") (class "Default")
      (node (ref "D2") (pin "1") (pinfunction "A_1") (pintype "passive"))
      (node (ref "R13") (pin "1") (pinfunction "R1_1") (pintype "passive"))
    )
    (net (code "63") (name "Net-(D3-A)") (class "Default")
      (node (ref "D3") (pin "1") (pinfunction "A_1") (pintype "passive"))
      (node (ref "R16") (pin "1") (pinfunction "R1_1") (pintype "passive"))
    )
    (net (code "64") (name "Net-(D6-A)") (class "Default")
      (node (ref "D6") (pin "1") (pinfunction "A_1") (pintype "passive"))
      (node (ref "R32") (pin "1") (pinfunction "R1_1") (pintype "passive"))
    )
    (net (code "65") (name "Net-(D6-K)") (class "Default")
      (node (ref "D6") (pin "2") (pinfunction "K_2") (pintype "passive"))
      (node (ref "Q2") (pin "3") (pinfunction "D_3") (pintype "passive"))
    )
    (net (code "66") (name "Net-(R39-R2)") (class "Default")
      (node (ref "R39") (pin "2") (pinfunction "R2_2") (pintype "passive"))
      (node (ref "R40") (pin "1") (pinfunction "R1_1") (pintype "passive"))
    )
    (net (code "67") (name "Net-(TP13-SIGNAL)") (class "Default")
      (node (ref "TP13") (pin "1") (pinfunction "SIGNAL_1") (pintype "passive"))
      (node (ref "U1") (pin "15") (pinfunction "PA3_15") (pintype "bidirectional"))
    )
    (net (code "68") (name "Net-(U1-RES5)") (class "Default")
      (node (ref "R37") (pin "1") (pinfunction "1_1") (pintype "passive"))
      (node (ref "U1") (pin "50") (pinfunction "RES5_50") (pintype "passive"))
    )
    (net (code "69") (name "VCC") (class "Default")
      (node (ref "C5") (pin "2") (pinfunction "C2_2") (pintype "passive"))
      (node (ref "C6") (pin "2") (pinfunction "C2_2") (pintype "passive"))
      (node (ref "R13") (pin "2") (pinfunction "R2_2") (pintype "passive"))
      (node (ref "R25") (pin "2") (pinfunction "R2_2") (pintype "passive"))
      (node (ref "U1") (pin "51") (pinfunction "VCC_51") (pintype "power_in"))
    )
    (net (code "70") (name "VDD") (class "Default")
      (node (ref "C1") (pin "2") (pinfunction "C2_2") (pintype "passive"))
      (node (ref "C11") (pin "2") (pinfunction "C2_2") (pintype "passive"))
      (node (ref "C12") (pin "2") (pinfunction "C2_2") (pintype "passive"))
      (node (ref "C2") (pin "2") (pinfunction "C2_2") (pintype "passive"))
      (node (ref "C3") (pin "2") (pinfunction "C2_2") (pintype "passive"))
      (node (ref "C4") (pin "2") (pinfunction "C2_2") (pintype "passive"))
      (node (ref "R1") (pin "1") (pinfunction "R1_1") (pintype "passive"))
      (node (ref "R11") (pin "2") (pinfunction "R2_2") (pintype "passive"))
      (node (ref "R2") (pin "1") (pinfunction "R1_1") (pintype "passive"))
      (node (ref "R20") (pin "2") (pinfunction "2_2") (pintype "passive"))
      (node (ref "R23") (pin "1") (pinfunction "R1_1") (pintype "passive"))
      (node (ref "R3") (pin "1") (pinfunction "R1_1") (pintype "passive"))
      (node (ref "R32") (pin "2") (pinfunction "R2_2") (pintype "passive"))
      (node (ref "R7") (pin "1") (pinfunction "R1_1") (pintype "passive"))
      (node (ref "U1") (pin "11") (pinfunction "VDDA_11") (pintype "power_in"))
      (node (ref "U1") (pin "22") (pinfunction "VDD_22") (pintype "power_in"))
      (node (ref "U1") (pin "3") (pinfunction "VDD_3") (pintype "power_in"))
      (node (ref "U2") (pin "5") (pinfunction "V+_5") (pintype "power_in"))
    )
    (net (code "71") (name "unconnected-(U1-NC-Pad32)") (class "Default")
      (node (ref "U1") (pin "32") (pinfunction "NC_32") (pintype "passive+no_connect"))
    )
    (net (code "72") (name "unconnected-(U1-NC-Pad36)") (class "Default")
      (node (ref "U1") (pin "36") (pinfunction "NC_36") (pintype "passive+no_connect"))
    )
    (net (code "73") (name "unconnected-(U1-NC-Pad37)") (class "Default")
      (node (ref "U1") (pin "37") (pinfunction "NC_37") (pintype "passive+no_connect"))
    )
    (net (code "74") (name "unconnected-(U1-NC-Pad38)") (class "Default")
      (node (ref "U1") (pin "38") (pinfunction "NC_38") (pintype "passive+no_connect"))
    )
    (net (code "75") (name "unconnected-(U1-NC-Pad39)") (class "Default")
      (node (ref "U1") (pin "39") (pinfunction "NC_39") (pintype "passive+no_connect"))
    )
    (net (code "76") (name "unconnected-(U1-NC-Pad43)") (class "Default")
      (node (ref "U1") (pin "43") (pinfunction "NC_43") (pintype "passive+no_connect"))
    )
    (net (code "77") (name "unconnected-(U1-NC-Pad44)") (class "Default")
      (node (ref "U1") (pin "44") (pinfunction "NC_44") (pintype "passive+no_connect"))
    )
    (net (code "78") (name "unconnected-(U1-NC-Pad45)") (class "Default")
      (node (ref "U1") (pin "45") (pinfunction "NC_45") (pintype "passive+no_connect"))
    )
    (net (code "79") (name "unconnected-(U1-NC-Pad49)") (class "Default")
      (node (ref "U1") (pin "49") (pinfunction "NC_49") (pintype "passive+no_connect"))
    )
    (net (code "80") (name "unconnected-(U1-PA12-Pad55)") (class "Default")
      (node (ref "U1") (pin "55") (pinfunction "PA12_55") (pintype "bidirectional+no_connect"))
    )
    (net (code "81") (name "unconnected-(U1-PB8-Pad1)") (class "Default")
      (node (ref "U1") (pin "1") (pinfunction "PB8_1") (pintype "bidirectional"))
    )
    (net (code "82") (name "unconnected-(U1-PC13-Pad4)") (class "Default")
      (node (ref "U1") (pin "4") (pinfunction "PC13_4") (pintype "bidirectional"))
    )
    (net (code "83") (name "unconnected-(U1-PC14-Pad5)") (class "Default")
      (node (ref "U1") (pin "5") (pinfunction "PC14_5") (pintype "bidirectional"))
    )
    (net (code "84") (name "unconnected-(U1-PC15-Pad6)") (class "Default")
      (node (ref "U1") (pin "6") (pinfunction "PC15_6") (pintype "bidirectional"))
    )
    (net (code "85") (name "unconnected-(U1-RES1-Pad52)") (class "Default")
      (node (ref "U1") (pin "52") (pinfunction "RES1_52") (pintype "passive+no_connect"))
    )
    (net (code "86") (name "unconnected-(U1-RES2-Pad53)") (class "Default")
      (node (ref "U1") (pin "53") (pinfunction "RES2_53") (pintype "passive+no_connect"))
    )
    (net (code "87") (name "unconnected-(U1-RES3-Pad54)") (class "Default")
      (node (ref "U1") (pin "54") (pinfunction "RES3_54") (pintype "passive+no_connect"))
    )
    (net (code "88") (name "unconnected-(U1-RES4-Pad31)") (class "Default")
      (node (ref "U1") (pin "31") (pinfunction "RES4_31") (pintype "passive+no_connect"))
    )
  )
)
